# Conexion_PCB2.net
KiCad netlist of a schematic drawn in Altium Designer
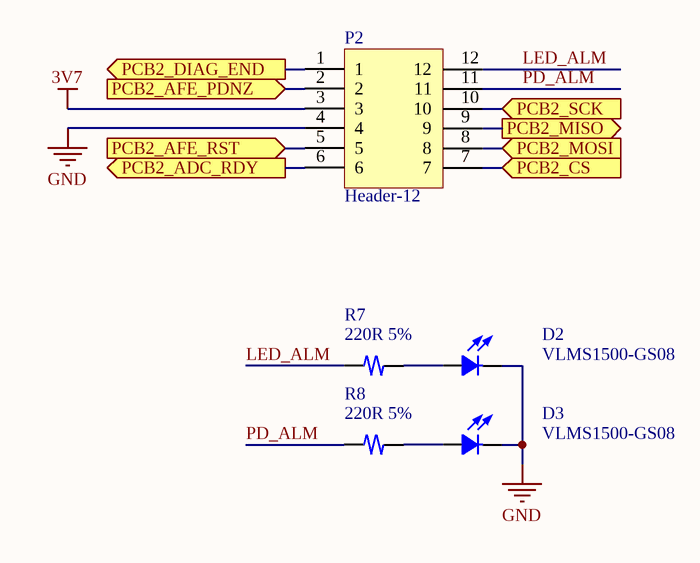
[diagram p0: Conexion_PCB2.SchDoc]

(export (version "E")
  (design (tool "Eeschema 10.0.6"))
  (components
    (comp (ref "D2")
      (value "VLMS1500-GS08")
      (footprint "L_0402")
      (description "LED Diode SMD 0402")
      (libsource (lib "Oxy_Lib") (part "Diode LED"))
    )
    (comp (ref "D3")
      (value "VLMS1500-GS08")
      (footprint "L_0402")
      (description "LED Diode SMD 0402")
      (libsource (lib "Oxy_Lib") (part "Diode LED"))
    )
    (comp (ref "P2")
      (value "Header-12")
      (footprint "HEADER 12")
      (description "Board to Board & Mezzanine Connector 0.8 BtB Molex PN: 53307-1271")
      (libsource (lib "Oxy_Lib") (part "12-Pin Header"))
    )
    (comp (ref "R7")
      (value "220R 5%")
      (footprint "R_0402")
      (description "Resistor SMD 0402")
      (libsource (lib "Oxy_Lib") (part "Resistor"))
    )
    (comp (ref "R8")
      (value "220R 5%")
      (footprint "R_0402")
      (description "Resistor SMD 0402")
      (libsource (lib "Oxy_Lib") (part "Resistor"))
    )
  )
  (nets
    (net (code "1") (name "/LED_ALM") (class "Default")
      (node (ref "P2") (pin "12") (pinfunction "12_12") (pintype "passive"))
      (node (ref "R7") (pin "1") (pinfunction "1_1") (pintype "passive"))
    )
    (net (code "2") (name "/PCB2_ADC_RDY") (class "Default")
      (node (ref "P2") (pin "6") (pinfunction "6_6") (pintype "passive"))
    )
    (net (code "3") (name "/PCB2_AFE_PDNZ") (class "Default")
      (node (ref "P2") (pin "2") (pinfunction "2_2") (pintype "passive"))
    )
    (net (code "4") (name "/PCB2_AFE_RST") (class "Default")
      (node (ref "P2") (pin "5") (pinfunction "5_5") (pintype "passive"))
    )
    (net (code "5") (name "/PCB2_CS") (class "Default")
      (node (ref "P2") (pin "7") (pinfunction "7_7") (pintype "passive"))
    )
    (net (code "6") (name "/PCB2_DIAG_END") (class "Default")
      (node (ref "P2") (pin "1") (pinfunction "1_1") (pintype "passive"))
    )
    (net (code "7") (name "/PCB2_MISO") (class "Default")
      (node (ref "P2") (pin "9") (pinfunction "9_9") (pintype "passive"))
    )
    (net (code "8") (name "/PCB2_MOSI") (class "Default")
      (node (ref "P2") (pin "8") (pinfunction "8_8") (pintype "passive"))
    )
    (net (code "9") (name "/PCB2_SCK") (class "Default")
      (node (ref "P2") (pin "10") (pinfunction "10_10") (pintype "passive"))
    )
    (net (code "10") (name "/PD_ALM") (class "Default")
      (node (ref "P2") (pin "11") (pinfunction "11_11") (pintype "passive"))
      (node (ref "R8") (pin "1") (pinfunction "1_1") (pintype "passive"))
    )
    (net (code "11") (name "3V7") (class "Default")
      (node (ref "P2") (pin "3") (pinfunction "3_3") (pintype "passive"))
    )
    (net (code "12") (name "GND") (class "Default")
      (node (ref "D2") (pin "2") (pinfunction "2_2") (pintype "passive"))
      (node (ref "D3") (pin "2") (pinfunction "2_2") (pintype "passive"))
      (node (ref "P2") (pin "4") (pinfunction "4_4") (pintype "passive"))
    )
    (net (code "13") (name "Net-(D2-Pad1)") (class "Default")
      (node (ref "D2") (pin "1") (pinfunction "1_1") (pintype "passive"))
      (node (ref "R7") (pin "2") (pinfunction "2_2") (pintype "passive"))
    )
    (net (code "14") (name "Net-(D3-Pad1)") (class "Default")
      (node (ref "D3") (pin "1") (pinfunction "1_1") (pintype "passive"))
      (node (ref "R8") (pin "2") (pinfunction "2_2") (pintype "passive"))
    )
  )
)
